# MMA8452Q-Breakout-v11.net
KiCad netlist of a schematic drawn in EAGLE
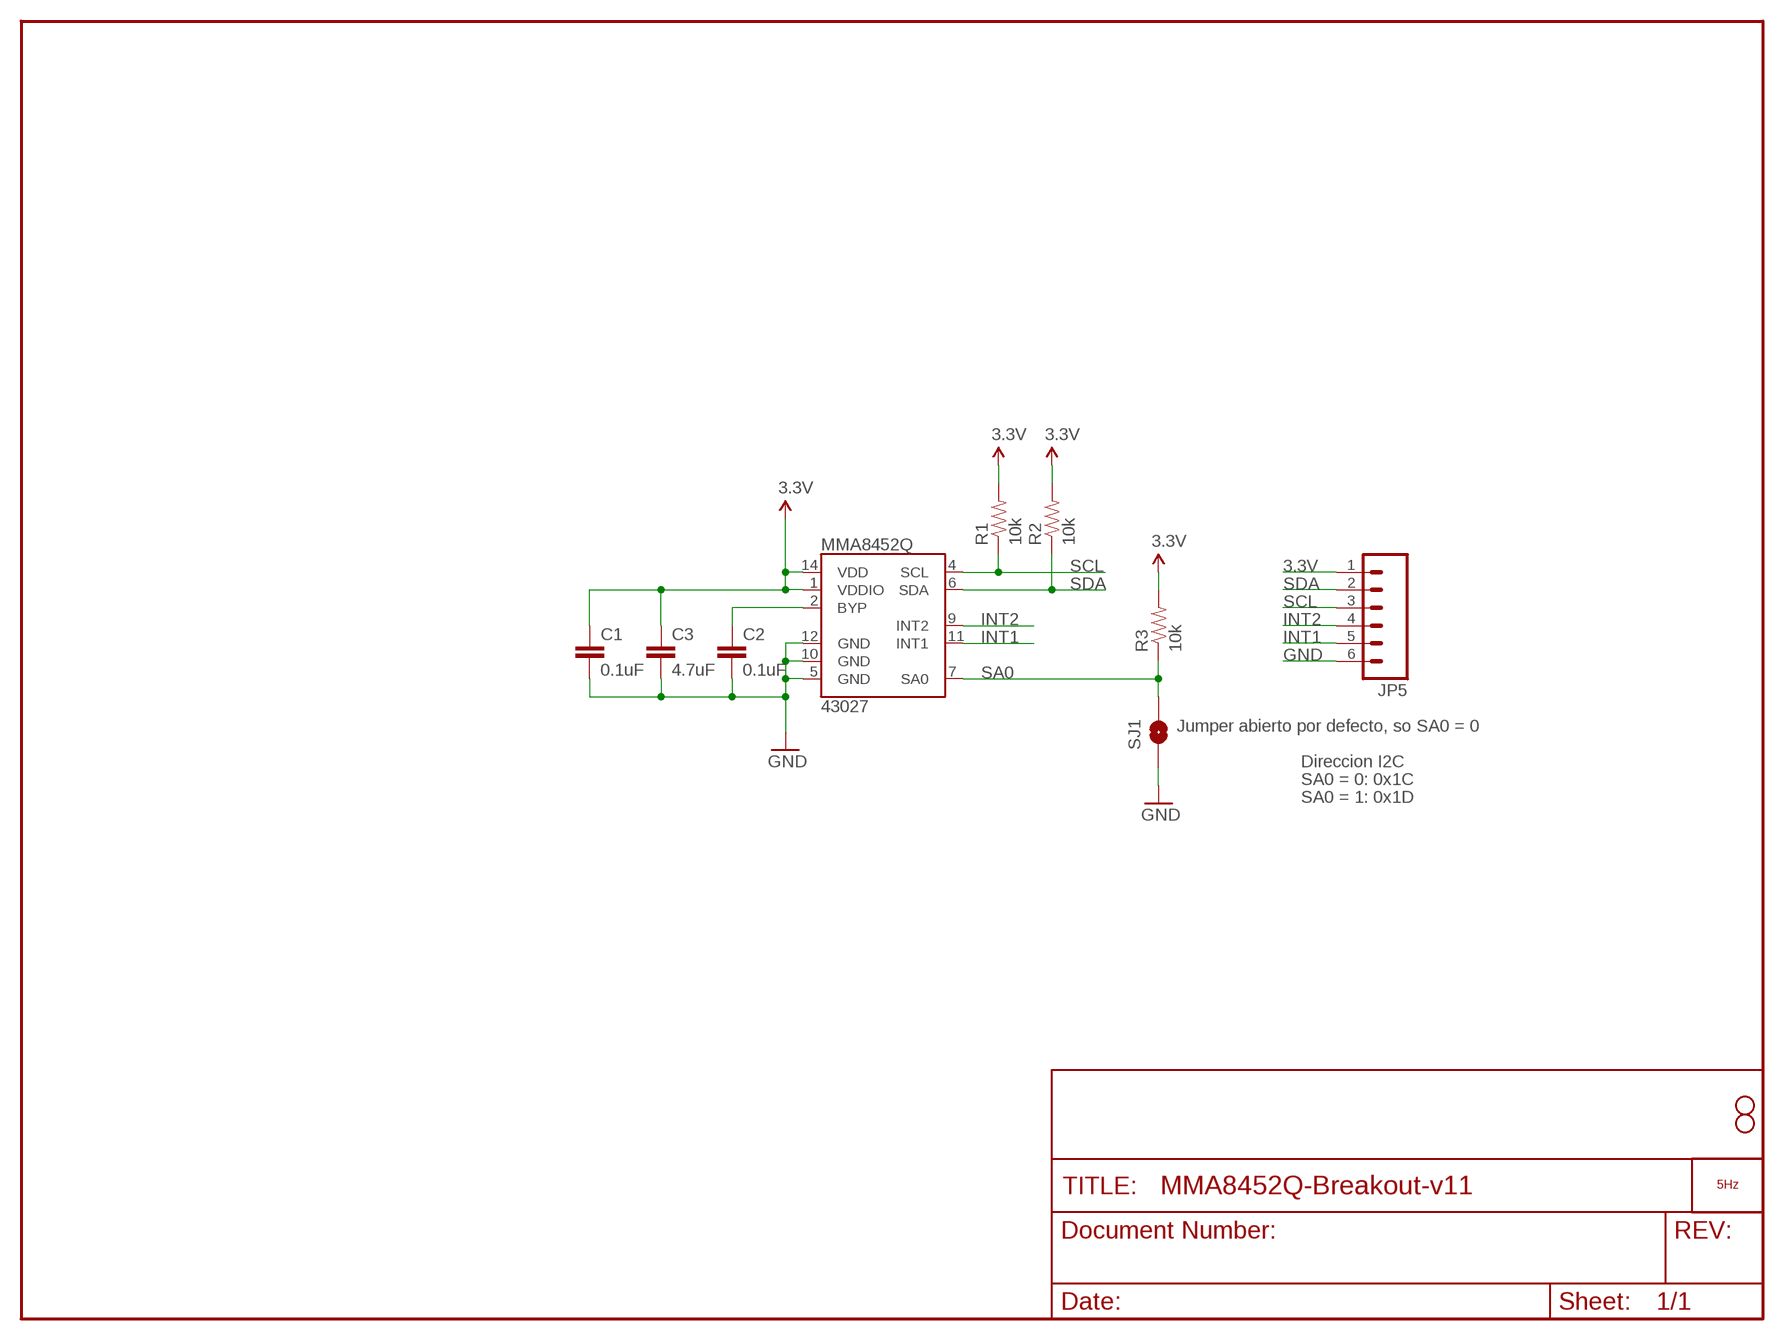
[diagram p0: schematic, sheet 1]

(export (version "E")
  (design (tool "Eeschema 10.0.6"))
  (components
    (comp (ref "C1")
      (value "0.1uF")
      (footprint "eagle-import:0402-CAP")
      (libsource (lib "eagle-import") (part "CAP0402-CAP"))
    )
    (comp (ref "C2")
      (value "0.1uF")
      (footprint "eagle-import:0402-CAP")
      (libsource (lib "eagle-import") (part "CAP0402-CAP"))
    )
    (comp (ref "C3")
      (value "4.7uF")
      (footprint "eagle-import:0402-CAP")
      (libsource (lib "eagle-import") (part "CAP0402-CAP"))
    )
    (comp (ref "JP3")
      (value "STAND-OFF")
      (footprint "eagle-import:STAND-OFF")
      (libsource (lib "eagle-import") (part "STAND-OFF"))
    )
    (comp (ref "JP4")
      (value "STAND-OFF")
      (footprint "eagle-import:STAND-OFF")
      (libsource (lib "eagle-import") (part "STAND-OFF"))
    )
    (comp (ref "JP5")
      (value "M06SIP")
      (footprint "eagle-import:1X06")
      (libsource (lib "eagle-import") (part "M06SIP"))
    )
    (comp (ref "LOGO1")
      (value "LOGO_5HZ_MAIN_5MM")
      (footprint "eagle-import:5HZ_LOGO_MAIN_5MM")
      (libsource (lib "eagle-import") (part "LOGO_5HZ_MAIN_5MM"))
    )
    (comp (ref "MMA8452Q")
      (value "43027")
      (footprint "eagle-import:QFN-16_0.5MM")
      (libsource (lib "eagle-import") (part "MMA8452Q"))
    )
    (comp (ref "R1")
      (value "10k")
      (footprint "eagle-import:0402-RES")
      (libsource (lib "eagle-import") (part "RESISTOR0402-RES"))
    )
    (comp (ref "R2")
      (value "10k")
      (footprint "eagle-import:0402-RES")
      (libsource (lib "eagle-import") (part "RESISTOR0402-RES"))
    )
    (comp (ref "R3")
      (value "10k")
      (footprint "eagle-import:0402-RES")
      (libsource (lib "eagle-import") (part "RESISTOR0402-RES"))
    )
    (comp (ref "SJ1")
      (value "SOLDERJUMPERNO")
      (footprint "eagle-import:SJ_2S-NO")
      (libsource (lib "eagle-import") (part "SOLDERJUMPERNO"))
    )
  )
  (nets
    (net (code "1") (name "/INT1") (class "Default")
      (node (ref "JP5") (pin "5") (pinfunction "5_5") (pintype "passive"))
      (node (ref "MMA8452Q") (pin "11") (pinfunction "INT1_11") (pintype "bidirectional"))
    )
    (net (code "2") (name "/INT2") (class "Default")
      (node (ref "JP5") (pin "4") (pinfunction "4_4") (pintype "passive"))
      (node (ref "MMA8452Q") (pin "9") (pinfunction "INT2_9") (pintype "bidirectional"))
    )
    (net (code "3") (name "/SA0") (class "Default")
      (node (ref "MMA8452Q") (pin "7") (pinfunction "SA0_7") (pintype "bidirectional"))
      (node (ref "R3") (pin "1") (pinfunction "1_1") (pintype "passive"))
      (node (ref "SJ1") (pin "2") (pinfunction "2_2") (pintype "passive"))
    )
    (net (code "4") (name "/SCL") (class "Default")
      (node (ref "JP5") (pin "3") (pinfunction "3_3") (pintype "passive"))
      (node (ref "MMA8452Q") (pin "4") (pinfunction "SCL_4") (pintype "bidirectional"))
      (node (ref "R1") (pin "1") (pinfunction "1_1") (pintype "passive"))
    )
    (net (code "5") (name "/SDA") (class "Default")
      (node (ref "JP5") (pin "2") (pinfunction "2_2") (pintype "passive"))
      (node (ref "MMA8452Q") (pin "6") (pinfunction "SDA_6") (pintype "bidirectional"))
      (node (ref "R2") (pin "1") (pinfunction "1_1") (pintype "passive"))
    )
    (net (code "6") (name "3.3V") (class "Default")
      (node (ref "C1") (pin "1") (pinfunction "1_1") (pintype "passive"))
      (node (ref "C3") (pin "1") (pinfunction "1_1") (pintype "passive"))
      (node (ref "JP5") (pin "1") (pinfunction "1_1") (pintype "passive"))
      (node (ref "MMA8452Q") (pin "1") (pinfunction "VDDIO_1") (pintype "bidirectional"))
      (node (ref "MMA8452Q") (pin "14") (pinfunction "VDD_14") (pintype "bidirectional"))
      (node (ref "R1") (pin "2") (pinfunction "2_2") (pintype "passive"))
      (node (ref "R2") (pin "2") (pinfunction "2_2") (pintype "passive"))
      (node (ref "R3") (pin "2") (pinfunction "2_2") (pintype "passive"))
    )
    (net (code "7") (name "GND") (class "Default")
      (node (ref "C1") (pin "2") (pinfunction "2_2") (pintype "passive"))
      (node (ref "C2") (pin "2") (pinfunction "2_2") (pintype "passive"))
      (node (ref "C3") (pin "2") (pinfunction "2_2") (pintype "passive"))
      (node (ref "JP5") (pin "6") (pinfunction "6_6") (pintype "passive"))
      (node (ref "MMA8452Q") (pin "10") (pinfunction "GND_10") (pintype "bidirectional"))
      (node (ref "MMA8452Q") (pin "12") (pinfunction "GND_12") (pintype "bidirectional"))
      (node (ref "MMA8452Q") (pin "5") (pinfunction "GND_5") (pintype "bidirectional"))
      (node (ref "SJ1") (pin "1") (pinfunction "1_1") (pintype "passive"))
    )
    (net (code "8") (name "Net-(MMA8452Q-BYP)") (class "Default")
      (node (ref "C2") (pin "1") (pinfunction "1_1") (pintype "passive"))
      (node (ref "MMA8452Q") (pin "2") (pinfunction "BYP_2") (pintype "bidirectional"))
    )
  )
)
